# clock.net
KiCad netlist of a schematic drawn in EAGLE
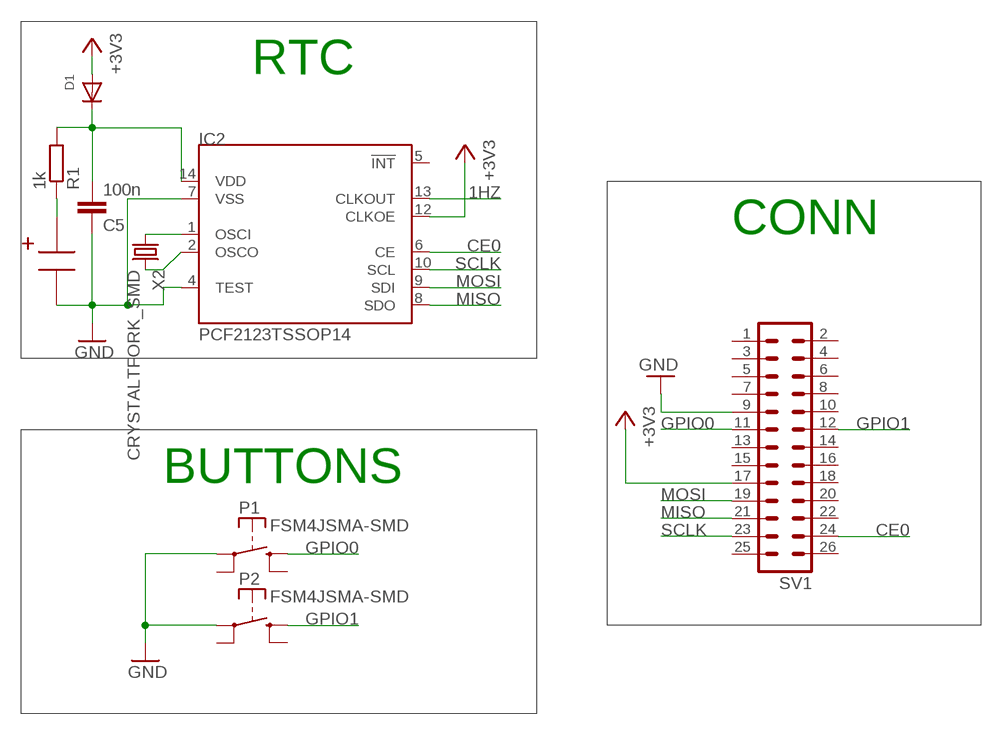
[diagram p0: schematic, sheet 1]

(export (version "E")
  (design (tool "Eeschema 10.0.6"))
  (components
    (comp (ref "C5")
      (value "100n")
      (footprint "eagle-import:C0603K")
      (libsource (lib "eagle-import") (part "C-EUC0603K"))
    )
    (comp (ref "D1")
      (value "DIODESOD-523")
      (footprint "eagle-import:SOD-523")
      (libsource (lib "eagle-import") (part "DIODESOD-523"))
    )
    (comp (ref "IC2")
      (value "PCF2123TSSOP14")
      (footprint "eagle-import:TSSOP14")
      (libsource (lib "eagle-import") (part "PCF2123TSSOP14"))
    )
    (comp (ref "P1")
      (value "FSM4JSMA-SMD")
      (footprint "eagle-import:FSM4JSMA-SMD")
      (libsource (lib "eagle-import") (part "FSM4JSMA-SMD"))
    )
    (comp (ref "P2")
      (value "FSM4JSMA-SMD")
      (footprint "eagle-import:FSM4JSMA-SMD")
      (libsource (lib "eagle-import") (part "FSM4JSMA-SMD"))
    )
    (comp (ref "R1")
      (value "1k")
      (footprint "eagle-import:R0603")
      (libsource (lib "eagle-import") (part "R-EU_R0603"))
    )
    (comp (ref "SV1")
      (value "MA13-2")
      (footprint "eagle-import:MA13-2")
      (libsource (lib "eagle-import") (part "MA13-2"))
    )
    (comp (ref "U$1")
      (value "DCK-3R3E224U-E")
      (footprint "eagle-import:SUPCAP-E")
      (libsource (lib "eagle-import") (part "DCK-3R3E224U-E"))
    )
    (comp (ref "X2")
      (value "CRYSTALTFORK_SMD")
      (footprint "eagle-import:TFORK_SMD")
      (libsource (lib "eagle-import") (part "CRYSTALTFORK_SMD"))
    )
  )
  (nets
    (net (code "1") (name "+3V3") (class "Default")
      (node (ref "D1") (pin "A") (pinfunction "A_A") (pintype "passive"))
      (node (ref "IC2") (pin "12") (pinfunction "CLKOE_12") (pintype "input"))
      (node (ref "SV1") (pin "17") (pinfunction "17_17") (pintype "passive"))
    )
    (net (code "2") (name "/1HZ") (class "Default")
      (node (ref "IC2") (pin "13") (pinfunction "CLKOUT_13") (pintype "output"))
    )
    (net (code "3") (name "/CE0") (class "Default")
      (node (ref "IC2") (pin "6") (pinfunction "CE_6") (pintype "input"))
      (node (ref "SV1") (pin "24") (pinfunction "24_24") (pintype "passive"))
    )
    (net (code "4") (name "/GPIO0") (class "Default")
      (node (ref "P1") (pin "P$3") (pinfunction "S_P$3") (pintype "passive"))
      (node (ref "SV1") (pin "11") (pinfunction "11_11") (pintype "passive"))
    )
    (net (code "5") (name "/GPIO1") (class "Default")
      (node (ref "P2") (pin "P$3") (pinfunction "S_P$3") (pintype "passive"))
      (node (ref "SV1") (pin "12") (pinfunction "12_12") (pintype "passive"))
    )
    (net (code "6") (name "/MISO") (class "Default")
      (node (ref "IC2") (pin "8") (pinfunction "SDO_8") (pintype "output"))
      (node (ref "SV1") (pin "21") (pinfunction "21_21") (pintype "passive"))
    )
    (net (code "7") (name "/MOSI") (class "Default")
      (node (ref "IC2") (pin "9") (pinfunction "SDI_9") (pintype "input"))
      (node (ref "SV1") (pin "19") (pinfunction "19_19") (pintype "passive"))
    )
    (net (code "8") (name "/SCLK") (class "Default")
      (node (ref "IC2") (pin "10") (pinfunction "SCL_10") (pintype "input"))
      (node (ref "SV1") (pin "23") (pinfunction "23_23") (pintype "passive"))
    )
    (net (code "9") (name "GND") (class "Default")
      (node (ref "C5") (pin "1") (pinfunction "1_1") (pintype "passive"))
      (node (ref "IC2") (pin "4") (pinfunction "TEST_4") (pintype "input"))
      (node (ref "IC2") (pin "7") (pinfunction "VSS_7") (pintype "power_in"))
      (node (ref "P1") (pin "P$1") (pinfunction "P_P$1") (pintype "passive"))
      (node (ref "P2") (pin "P$1") (pinfunction "P_P$1") (pintype "passive"))
      (node (ref "SV1") (pin "9") (pinfunction "9_9") (pintype "passive"))
      (node (ref "U$1") (pin "-") (pinfunction "-_-") (pintype "bidirectional"))
    )
    (net (code "10") (name "Net-(D1-C)") (class "Default")
      (node (ref "C5") (pin "2") (pinfunction "2_2") (pintype "passive"))
      (node (ref "D1") (pin "K") (pinfunction "C_K") (pintype "passive"))
      (node (ref "IC2") (pin "14") (pinfunction "VDD_14") (pintype "power_in"))
      (node (ref "R1") (pin "2") (pinfunction "2_2") (pintype "passive"))
    )
    (net (code "11") (name "Net-(IC2-OSCI)") (class "Default")
      (node (ref "IC2") (pin "1") (pinfunction "OSCI_1") (pintype "input"))
      (node (ref "X2") (pin "2") (pinfunction "1_2") (pintype "passive"))
    )
    (net (code "12") (name "Net-(IC2-OSCO)") (class "Default")
      (node (ref "IC2") (pin "2") (pinfunction "OSCO_2") (pintype "input"))
      (node (ref "X2") (pin "3") (pinfunction "2_3") (pintype "passive"))
    )
    (net (code "13") (name "Net-(R1-Pad1)") (class "Default")
      (node (ref "R1") (pin "1") (pinfunction "1_1") (pintype "passive"))
      (node (ref "U$1") (pin "+") (pinfunction "+_+") (pintype "bidirectional"))
    )
    (net (code "14") (name "unconnected-(IC2-~{INT}-Pad5)") (class "Default")
      (node (ref "IC2") (pin "5") (pinfunction "~{INT}_5") (pintype "output"))
    )
    (net (code "15") (name "unconnected-(P1-P-PadP$2)") (class "Default")
      (node (ref "P1") (pin "P$2") (pinfunction "P_P$2") (pintype "passive"))
    )
    (net (code "16") (name "unconnected-(P1-S-PadP$4)") (class "Default")
      (node (ref "P1") (pin "P$4") (pinfunction "S_P$4") (pintype "passive"))
    )
    (net (code "17") (name "unconnected-(P2-P-PadP$2)") (class "Default")
      (node (ref "P2") (pin "P$2") (pinfunction "P_P$2") (pintype "passive"))
    )
    (net (code "18") (name "unconnected-(P2-S-PadP$4)") (class "Default")
      (node (ref "P2") (pin "P$4") (pinfunction "S_P$4") (pintype "passive"))
    )
    (net (code "19") (name "unconnected-(SV1-Pad1)") (class "Default")
      (node (ref "SV1") (pin "1") (pinfunction "1_1") (pintype "passive"))
    )
    (net (code "20") (name "unconnected-(SV1-Pad2)") (class "Default")
      (node (ref "SV1") (pin "2") (pinfunction "2_2") (pintype "passive"))
    )
    (net (code "21") (name "unconnected-(SV1-Pad3)") (class "Default")
      (node (ref "SV1") (pin "3") (pinfunction "3_3") (pintype "passive"))
    )
    (net (code "22") (name "unconnected-(SV1-Pad4)") (class "Default")
      (node (ref "SV1") (pin "4") (pinfunction "4_4") (pintype "passive"))
    )
    (net (code "23") (name "unconnected-(SV1-Pad5)") (class "Default")
      (node (ref "SV1") (pin "5") (pinfunction "5_5") (pintype "passive"))
    )
    (net (code "24") (name "unconnected-(SV1-Pad6)") (class "Default")
      (node (ref "SV1") (pin "6") (pinfunction "6_6") (pintype "passive"))
    )
    (net (code "25") (name "unconnected-(SV1-Pad7)") (class "Default")
      (node (ref "SV1") (pin "7") (pinfunction "7_7") (pintype "passive"))
    )
    (net (code "26") (name "unconnected-(SV1-Pad8)") (class "Default")
      (node (ref "SV1") (pin "8") (pinfunction "8_8") (pintype "passive"))
    )
    (net (code "27") (name "unconnected-(SV1-Pad10)") (class "Default")
      (node (ref "SV1") (pin "10") (pinfunction "10_10") (pintype "passive"))
    )
    (net (code "28") (name "unconnected-(SV1-Pad13)") (class "Default")
      (node (ref "SV1") (pin "13") (pinfunction "13_13") (pintype "passive"))
    )
    (net (code "29") (name "unconnected-(SV1-Pad14)") (class "Default")
      (node (ref "SV1") (pin "14") (pinfunction "14_14") (pintype "passive"))
    )
    (net (code "30") (name "unconnected-(SV1-Pad15)") (class "Default")
      (node (ref "SV1") (pin "15") (pinfunction "15_15") (pintype "passive"))
    )
    (net (code "31") (name "unconnected-(SV1-Pad16)") (class "Default")
      (node (ref "SV1") (pin "16") (pinfunction "16_16") (pintype "passive"))
    )
    (net (code "32") (name "unconnected-(SV1-Pad18)") (class "Default")
      (node (ref "SV1") (pin "18") (pinfunction "18_18") (pintype "passive"))
    )
    (net (code "33") (name "unconnected-(SV1-Pad20)") (class "Default")
      (node (ref "SV1") (pin "20") (pinfunction "20_20") (pintype "passive"))
    )
    (net (code "34") (name "unconnected-(SV1-Pad22)") (class "Default")
      (node (ref "SV1") (pin "22") (pinfunction "22_22") (pintype "passive"))
    )
    (net (code "35") (name "unconnected-(SV1-Pad25)") (class "Default")
      (node (ref "SV1") (pin "25") (pinfunction "25_25") (pintype "passive"))
    )
    (net (code "36") (name "unconnected-(SV1-Pad26)") (class "Default")
      (node (ref "SV1") (pin "26") (pinfunction "26_26") (pintype "passive"))
    )
  )
)
